# Glint_module_rev_A_-_hand_solder.net
KiCad netlist of a schematic drawn in EAGLE
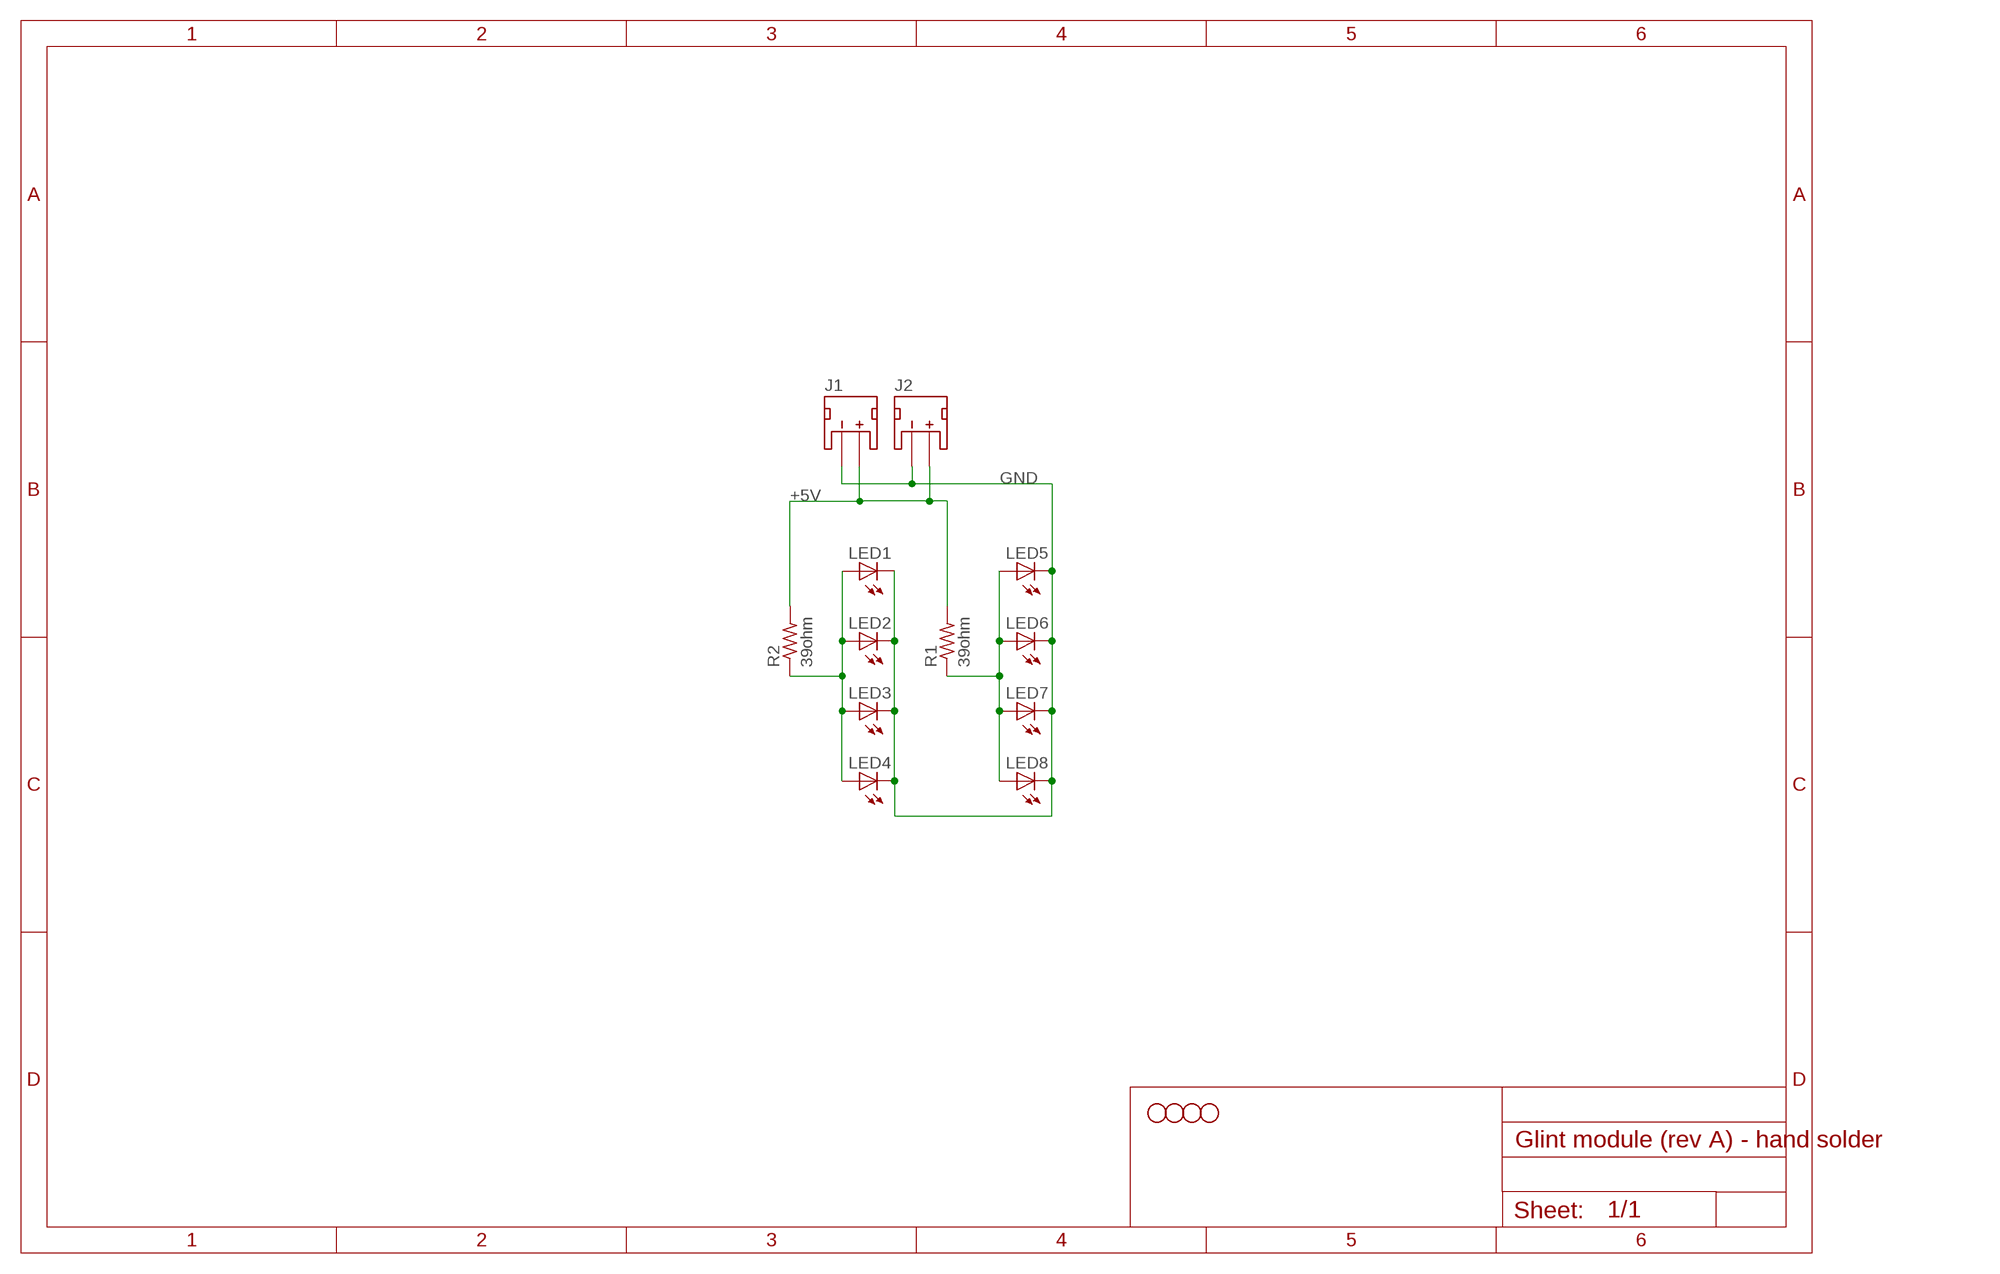
[diagram p0: schematic, sheet 1]

(export (version "E")
  (design (tool "Eeschema 10.0.6"))
  (components
    (comp (ref "J1")
      (value "JST_2MM_MALE")
      (footprint "eagle-import:JST-2-SMD")
      (libsource (lib "eagle-import") (part "JST_2MM_MALE"))
    )
    (comp (ref "J2")
      (value "JST_2MM_MALE")
      (footprint "eagle-import:JST-2-SMD")
      (libsource (lib "eagle-import") (part "JST_2MM_MALE"))
    )
    (comp (ref "LED1")
      (value "LED5MM")
      (footprint "eagle-import:LED5MM")
      (libsource (lib "eagle-import") (part "LED5MM"))
    )
    (comp (ref "LED2")
      (value "LED5MM")
      (footprint "eagle-import:LED5MM")
      (libsource (lib "eagle-import") (part "LED5MM"))
    )
    (comp (ref "LED3")
      (value "LED5MM")
      (footprint "eagle-import:LED5MM")
      (libsource (lib "eagle-import") (part "LED5MM"))
    )
    (comp (ref "LED4")
      (value "LED5MM")
      (footprint "eagle-import:LED5MM")
      (libsource (lib "eagle-import") (part "LED5MM"))
    )
    (comp (ref "LED5")
      (value "LED5MM")
      (footprint "eagle-import:LED5MM")
      (libsource (lib "eagle-import") (part "LED5MM"))
    )
    (comp (ref "LED6")
      (value "LED5MM")
      (footprint "eagle-import:LED5MM")
      (libsource (lib "eagle-import") (part "LED5MM"))
    )
    (comp (ref "LED7")
      (value "LED5MM")
      (footprint "eagle-import:LED5MM")
      (libsource (lib "eagle-import") (part "LED5MM"))
    )
    (comp (ref "LED8")
      (value "LED5MM")
      (footprint "eagle-import:LED5MM")
      (libsource (lib "eagle-import") (part "LED5MM"))
    )
    (comp (ref "R1")
      (value "39ohm")
      (footprint "eagle-import:0309_10")
      (libsource (lib "eagle-import") (part "R-US_0309/10"))
    )
    (comp (ref "R2")
      (value "39ohm")
      (footprint "eagle-import:0309_10")
      (libsource (lib "eagle-import") (part "R-US_0309/10"))
    )
    (comp (ref "STANDOFF1")
      (value "STAND-OFF")
      (footprint "eagle-import:STAND-OFF")
      (libsource (lib "eagle-import") (part "STAND-OFF"))
    )
    (comp (ref "STANDOFF2")
      (value "STAND-OFF")
      (footprint "eagle-import:STAND-OFF")
      (libsource (lib "eagle-import") (part "STAND-OFF"))
    )
    (comp (ref "STANDOFF3")
      (value "STAND-OFF")
      (footprint "eagle-import:STAND-OFF")
      (libsource (lib "eagle-import") (part "STAND-OFF"))
    )
    (comp (ref "STANDOFF4")
      (value "STAND-OFF")
      (footprint "eagle-import:STAND-OFF")
      (libsource (lib "eagle-import") (part "STAND-OFF"))
    )
  )
  (nets
    (net (code "1") (name "/+5V") (class "Default")
      (node (ref "J1") (pin "2") (pinfunction "+_2") (pintype "bidirectional"))
      (node (ref "J2") (pin "2") (pinfunction "+_2") (pintype "bidirectional"))
      (node (ref "R1") (pin "2") (pinfunction "2_2") (pintype "passive"))
      (node (ref "R2") (pin "2") (pinfunction "2_2") (pintype "passive"))
    )
    (net (code "2") (name "/GND") (class "Default")
      (node (ref "J1") (pin "1") (pinfunction "-_1") (pintype "bidirectional"))
      (node (ref "J2") (pin "1") (pinfunction "-_1") (pintype "bidirectional"))
      (node (ref "LED1") (pin "K") (pinfunction "C_K") (pintype "passive"))
      (node (ref "LED2") (pin "K") (pinfunction "C_K") (pintype "passive"))
      (node (ref "LED3") (pin "K") (pinfunction "C_K") (pintype "passive"))
      (node (ref "LED4") (pin "K") (pinfunction "C_K") (pintype "passive"))
      (node (ref "LED5") (pin "K") (pinfunction "C_K") (pintype "passive"))
      (node (ref "LED6") (pin "K") (pinfunction "C_K") (pintype "passive"))
      (node (ref "LED7") (pin "K") (pinfunction "C_K") (pintype "passive"))
      (node (ref "LED8") (pin "K") (pinfunction "C_K") (pintype "passive"))
    )
    (net (code "3") (name "Net-(LED1-PadA)") (class "Default")
      (node (ref "LED1") (pin "A") (pinfunction "A_A") (pintype "passive"))
      (node (ref "LED2") (pin "A") (pinfunction "A_A") (pintype "passive"))
      (node (ref "LED3") (pin "A") (pinfunction "A_A") (pintype "passive"))
      (node (ref "LED4") (pin "A") (pinfunction "A_A") (pintype "passive"))
      (node (ref "R2") (pin "1") (pinfunction "1_1") (pintype "passive"))
    )
    (net (code "4") (name "Net-(LED5-PadA)") (class "Default")
      (node (ref "LED5") (pin "A") (pinfunction "A_A") (pintype "passive"))
      (node (ref "LED6") (pin "A") (pinfunction "A_A") (pintype "passive"))
      (node (ref "LED7") (pin "A") (pinfunction "A_A") (pintype "passive"))
      (node (ref "LED8") (pin "A") (pinfunction "A_A") (pintype "passive"))
      (node (ref "R1") (pin "1") (pinfunction "1_1") (pintype "passive"))
    )
    (net (code "5") (name "unconnected-(J1-PAD1-PadNC1)") (class "Default")
      (node (ref "J1") (pin "NC1") (pinfunction "PAD1_NC1") (pintype "bidirectional"))
    )
    (net (code "6") (name "unconnected-(J1-PAD2-PadNC2)") (class "Default")
      (node (ref "J1") (pin "NC2") (pinfunction "PAD2_NC2") (pintype "bidirectional"))
    )
    (net (code "7") (name "unconnected-(J2-PAD1-PadNC1)") (class "Default")
      (node (ref "J2") (pin "NC1") (pinfunction "PAD1_NC1") (pintype "bidirectional"))
    )
    (net (code "8") (name "unconnected-(J2-PAD2-PadNC2)") (class "Default")
      (node (ref "J2") (pin "NC2") (pinfunction "PAD2_NC2") (pintype "bidirectional"))
    )
  )
)
